# TPS65131.net
KiCad netlist of a schematic drawn in Altium Designer
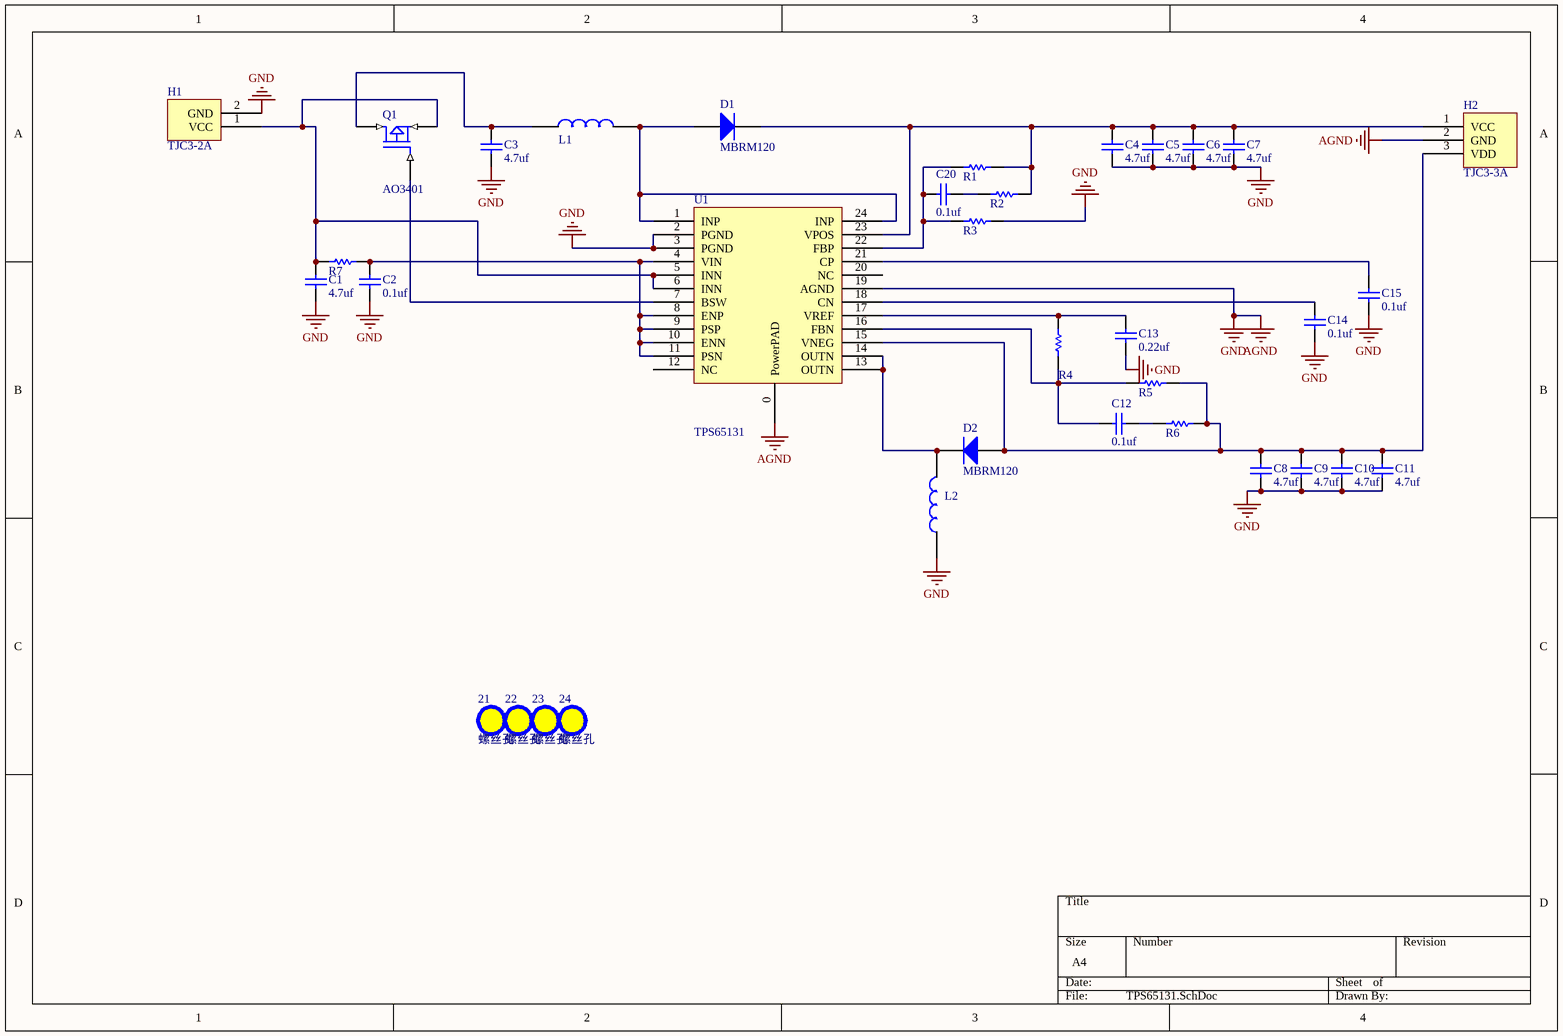
[diagram p0: TPS65131.SchDoc]

(export (version "E")
  (design (tool "Eeschema 10.0.6"))
  (components
    (comp (ref "21") (value "螺丝孔") (footprint "固定过孔") (libsource (lib "Schlib1") (part "螺丝孔")))
    (comp (ref "22") (value "螺丝孔") (footprint "固定过孔") (libsource (lib "Schlib1") (part "螺丝孔")))
    (comp (ref "23") (value "螺丝孔") (footprint "固定过孔") (libsource (lib "Schlib1") (part "螺丝孔")))
    (comp (ref "24") (value "螺丝孔") (footprint "固定过孔") (libsource (lib "Schlib1") (part "螺丝孔")))
    (comp (ref "C1")
      (value "Cap1")
      (footprint "0805")
      (fields (field (name "值") "4.7uf"))
      (libsource (lib "Schlib1") (part "Cap1"))
    )
    (comp (ref "C2")
      (value "Cap1")
      (footprint "0805")
      (fields (field (name "值") "0.1uf"))
      (libsource (lib "Schlib1") (part "Cap1"))
    )
    (comp (ref "C3")
      (value "Cap1")
      (footprint "0805")
      (fields (field (name "值") "4.7uf"))
      (libsource (lib "Schlib1") (part "Cap1"))
    )
    (comp (ref "C4")
      (value "Cap1")
      (footprint "0805")
      (fields (field (name "值") "4.7uf"))
      (libsource (lib "Schlib1") (part "Cap1"))
    )
    (comp (ref "C5")
      (value "Cap1")
      (footprint "0805")
      (fields (field (name "值") "4.7uf"))
      (libsource (lib "Schlib1") (part "Cap1"))
    )
    (comp (ref "C6")
      (value "Cap1")
      (footprint "0805")
      (fields (field (name "值") "4.7uf"))
      (libsource (lib "Schlib1") (part "Cap1"))
    )
    (comp (ref "C7")
      (value "Cap1")
      (footprint "0805")
      (fields (field (name "值") "4.7uf"))
      (libsource (lib "Schlib1") (part "Cap1"))
    )
    (comp (ref "C8")
      (value "Cap1")
      (footprint "0805")
      (fields (field (name "值") "4.7uf"))
      (libsource (lib "Schlib1") (part "Cap1"))
    )
    (comp (ref "C9")
      (value "Cap1")
      (footprint "0805")
      (fields (field (name "值") "4.7uf"))
      (libsource (lib "Schlib1") (part "Cap1"))
    )
    (comp (ref "C10")
      (value "Cap1")
      (footprint "0805")
      (fields (field (name "值") "4.7uf"))
      (libsource (lib "Schlib1") (part "Cap1"))
    )
    (comp (ref "C11")
      (value "Cap1")
      (footprint "0805")
      (fields (field (name "值") "4.7uf"))
      (libsource (lib "Schlib1") (part "Cap1"))
    )
    (comp (ref "C12")
      (value "Cap1")
      (footprint "0805")
      (fields (field (name "值") "0.1uf"))
      (libsource (lib "Schlib1") (part "Cap1"))
    )
    (comp (ref "C13")
      (value "Cap1")
      (footprint "0805")
      (fields (field (name "值") "0.22uf"))
      (libsource (lib "Schlib1") (part "Cap1"))
    )
    (comp (ref "C14")
      (value "Cap1")
      (footprint "0805")
      (fields (field (name "值") "0.1uf"))
      (libsource (lib "Schlib1") (part "Cap1"))
    )
    (comp (ref "C15")
      (value "Cap1")
      (footprint "0805")
      (fields (field (name "值") "0.1uf"))
      (libsource (lib "Schlib1") (part "Cap1"))
    )
    (comp (ref "C20")
      (value "Cap1")
      (footprint "0805")
      (fields (field (name "值") "0.1uf"))
      (libsource (lib "Schlib1") (part "Cap1"))
    )
    (comp (ref "D1") (value "MBRM120") (footprint "SMB") (libsource (lib "Schlib1") (part "MBRM120")))
    (comp (ref "D2") (value "MBRM120") (footprint "SMB") (libsource (lib "Schlib1") (part "MBRM120")))
    (comp (ref "H1") (value "TJC3-2A") (footprint "TJC3-2A") (libsource (lib "Schlib1") (part "TJC3-2A")))
    (comp (ref "H2") (value "TJC3-3A") (footprint "TJC3-3A") (libsource (lib "Schlib1") (part "TJC3-3A")))
    (comp (ref "L1") (value "SMD") (footprint "功率电感-12x12 - duplicate") (libsource (lib "") (part "功率电感_1")))
    (comp (ref "L2")
      (value "SMD")
      (footprint "功率电感-12x12 - duplicate")
      (libsource (lib "Schlib1") (part "功率电感"))
    )
    (comp (ref "Q1") (value "AO3401") (footprint "SOT-23") (libsource (lib "Schlib1") (part "AO3401")))
    (comp (ref "R1") (value "RES") (footprint "0805") (libsource (lib "Schlib1") (part "RES")))
    (comp (ref "R2") (value "RES") (footprint "0805") (libsource (lib "Schlib1") (part "RES")))
    (comp (ref "R3") (value "RES") (footprint "0805") (libsource (lib "Schlib1") (part "RES")))
    (comp (ref "R4") (value "RES") (footprint "0805") (libsource (lib "Schlib1") (part "RES")))
    (comp (ref "R5") (value "RES") (footprint "0805") (libsource (lib "Schlib1") (part "RES")))
    (comp (ref "R6") (value "RES") (footprint "0805") (libsource (lib "Schlib1") (part "RES")))
    (comp (ref "R7") (value "RES") (footprint "0805") (libsource (lib "Schlib1") (part "RES")))
    (comp (ref "U1")
      (value "TPS65131")
      (footprint "LC-QFN-24_4x4x05P")
      (libsource (lib "Schlib1") (part "TPS65131"))
    )
  )
  (nets
    (net (code "1") (name "AGND") (class "Default")
      (node (ref "C1") (pin "1") (pinfunction "1_1") (pintype "passive"))
      (node (ref "C10") (pin "1") (pinfunction "1_1") (pintype "passive"))
      (node (ref "C11") (pin "1") (pinfunction "1_1") (pintype "passive"))
      (node (ref "C13") (pin "2") (pinfunction "2_2") (pintype "passive"))
      (node (ref "C14") (pin "2") (pinfunction "2_2") (pintype "passive"))
      (node (ref "C15") (pin "2") (pinfunction "2_2") (pintype "passive"))
      (node (ref "C2") (pin "1") (pinfunction "1_1") (pintype "passive"))
      (node (ref "C3") (pin "1") (pinfunction "1_1") (pintype "passive"))
      (node (ref "C4") (pin "1") (pinfunction "1_1") (pintype "passive"))
      (node (ref "C5") (pin "1") (pinfunction "1_1") (pintype "passive"))
      (node (ref "C6") (pin "1") (pinfunction "1_1") (pintype "passive"))
      (node (ref "C7") (pin "1") (pinfunction "1_1") (pintype "passive"))
      (node (ref "C8") (pin "1") (pinfunction "1_1") (pintype "passive"))
      (node (ref "C9") (pin "1") (pinfunction "1_1") (pintype "passive"))
      (node (ref "H1") (pin "2") (pinfunction "GND_2") (pintype "passive"))
      (node (ref "H2") (pin "2") (pinfunction "GND_2") (pintype "passive"))
      (node (ref "L2") (pin "1") (pintype "passive"))
      (node (ref "R3") (pin "2") (pinfunction "2_2") (pintype "passive"))
      (node (ref "U1") (pin "0") (pinfunction "PowerPAD_0") (pintype "passive"))
      (node (ref "U1") (pin "19") (pinfunction "AGND_19") (pintype "passive"))
      (node (ref "U1") (pin "2") (pinfunction "PGND_2") (pintype "passive"))
      (node (ref "U1") (pin "3") (pinfunction "PGND_3") (pintype "passive"))
    )
    (net (code "2") (name "Net-(C12-Pad1)") (class "Default")
      (node (ref "C12") (pin "1") (pinfunction "1_1") (pintype "passive"))
      (node (ref "R6") (pin "2") (pinfunction "2_2") (pintype "passive"))
    )
    (net (code "3") (name "Net-(C20-Pad2)") (class "Default")
      (node (ref "C20") (pin "2") (pinfunction "2_2") (pintype "passive"))
      (node (ref "R2") (pin "1") (pinfunction "1_1") (pintype "passive"))
    )
    (net (code "4") (name "Net-(D1-A)") (class "Default")
      (node (ref "D1") (pin "1") (pinfunction "A_1") (pintype "passive"))
      (node (ref "L1") (pin "2") (pintype "passive"))
      (node (ref "U1") (pin "1") (pinfunction "INP_1") (pintype "passive"))
      (node (ref "U1") (pin "24") (pinfunction "INP_24") (pintype "passive"))
    )
    (net (code "5") (name "Net-(D1-K)") (class "Default")
      (node (ref "C4") (pin "2") (pinfunction "2_2") (pintype "passive"))
      (node (ref "C5") (pin "2") (pinfunction "2_2") (pintype "passive"))
      (node (ref "C6") (pin "2") (pinfunction "2_2") (pintype "passive"))
      (node (ref "C7") (pin "2") (pinfunction "2_2") (pintype "passive"))
      (node (ref "D1") (pin "2") (pinfunction "K_2") (pintype "passive"))
      (node (ref "H2") (pin "1") (pinfunction "VCC_1") (pintype "passive"))
      (node (ref "R1") (pin "2") (pinfunction "2_2") (pintype "passive"))
      (node (ref "R2") (pin "2") (pinfunction "2_2") (pintype "passive"))
      (node (ref "U1") (pin "23") (pinfunction "VPOS_23") (pintype "passive"))
    )
    (net (code "6") (name "Net-(D2-A)") (class "Default")
      (node (ref "C10") (pin "2") (pinfunction "2_2") (pintype "passive"))
      (node (ref "C11") (pin "2") (pinfunction "2_2") (pintype "passive"))
      (node (ref "C8") (pin "2") (pinfunction "2_2") (pintype "passive"))
      (node (ref "C9") (pin "2") (pinfunction "2_2") (pintype "passive"))
      (node (ref "D2") (pin "1") (pinfunction "A_1") (pintype "passive"))
      (node (ref "H2") (pin "3") (pinfunction "VDD_3") (pintype "passive"))
      (node (ref "R5") (pin "1") (pinfunction "1_1") (pintype "passive"))
      (node (ref "R6") (pin "1") (pinfunction "1_1") (pintype "passive"))
      (node (ref "U1") (pin "15") (pinfunction "VNEG_15") (pintype "passive"))
    )
    (net (code "7") (name "Net-(D2-K)") (class "Default")
      (node (ref "D2") (pin "2") (pinfunction "K_2") (pintype "passive"))
      (node (ref "L2") (pin "2") (pintype "passive"))
      (node (ref "U1") (pin "13") (pinfunction "OUTN_13") (pintype "passive"))
      (node (ref "U1") (pin "14") (pinfunction "OUTN_14") (pintype "passive"))
    )
    (net (code "8") (name "Net-(H1-VCC)") (class "Default")
      (node (ref "C1") (pin "2") (pinfunction "2_2") (pintype "passive"))
      (node (ref "H1") (pin "1") (pinfunction "VCC_1") (pintype "passive"))
      (node (ref "Q1") (pin "3") (pinfunction "S_3") (pintype "input"))
      (node (ref "R7") (pin "1") (pinfunction "1_1") (pintype "passive"))
      (node (ref "U1") (pin "5") (pinfunction "INN_5") (pintype "passive"))
      (node (ref "U1") (pin "6") (pinfunction "INN_6") (pintype "passive"))
    )
    (net (code "9") (name "Net-(Q1-D)") (class "Default")
      (node (ref "C3") (pin "2") (pinfunction "2_2") (pintype "passive"))
      (node (ref "L1") (pin "1") (pintype "passive"))
      (node (ref "Q1") (pin "2") (pinfunction "D_2") (pintype "input"))
    )
    (net (code "10") (name "Net-(Q1-G)") (class "Default")
      (node (ref "Q1") (pin "1") (pinfunction "G_1") (pintype "input"))
      (node (ref "U1") (pin "7") (pinfunction "BSW_7") (pintype "passive"))
    )
    (net (code "11") (name "Net-(U1-CN)") (class "Default")
      (node (ref "C14") (pin "1") (pinfunction "1_1") (pintype "passive"))
      (node (ref "U1") (pin "18") (pinfunction "CN_18") (pintype "passive"))
    )
    (net (code "12") (name "Net-(U1-CP)") (class "Default")
      (node (ref "C15") (pin "1") (pinfunction "1_1") (pintype "passive"))
      (node (ref "U1") (pin "21") (pinfunction "CP_21") (pintype "passive"))
    )
    (net (code "13") (name "Net-(U1-ENN)") (class "Default")
      (node (ref "C2") (pin "2") (pinfunction "2_2") (pintype "passive"))
      (node (ref "R7") (pin "2") (pinfunction "2_2") (pintype "passive"))
      (node (ref "U1") (pin "10") (pinfunction "ENN_10") (pintype "passive"))
      (node (ref "U1") (pin "11") (pinfunction "PSN_11") (pintype "passive"))
      (node (ref "U1") (pin "4") (pinfunction "VIN_4") (pintype "passive"))
      (node (ref "U1") (pin "8") (pinfunction "ENP_8") (pintype "passive"))
      (node (ref "U1") (pin "9") (pinfunction "PSP_9") (pintype "passive"))
    )
    (net (code "14") (name "Net-(U1-FBN)") (class "Default")
      (node (ref "C12") (pin "2") (pinfunction "2_2") (pintype "passive"))
      (node (ref "R4") (pin "1") (pinfunction "1_1") (pintype "passive"))
      (node (ref "R5") (pin "2") (pinfunction "2_2") (pintype "passive"))
      (node (ref "U1") (pin "16") (pinfunction "FBN_16") (pintype "passive"))
    )
    (net (code "15") (name "Net-(U1-FBP)") (class "Default")
      (node (ref "C20") (pin "1") (pinfunction "1_1") (pintype "passive"))
      (node (ref "R1") (pin "1") (pinfunction "1_1") (pintype "passive"))
      (node (ref "R3") (pin "1") (pinfunction "1_1") (pintype "passive"))
      (node (ref "U1") (pin "22") (pinfunction "FBP_22") (pintype "passive"))
    )
    (net (code "16") (name "Net-(U1-VREF)") (class "Default")
      (node (ref "C13") (pin "1") (pinfunction "1_1") (pintype "passive"))
      (node (ref "R4") (pin "2") (pinfunction "2_2") (pintype "passive"))
      (node (ref "U1") (pin "17") (pinfunction "VREF_17") (pintype "passive"))
    )
    (net (code "17") (name "unconnected-(U1-NC-Pad12)") (class "Default")
      (node (ref "U1") (pin "12") (pinfunction "NC_12") (pintype "passive"))
    )
    (net (code "18") (name "unconnected-(U1-NC-Pad20)") (class "Default")
      (node (ref "U1") (pin "20") (pinfunction "NC_20") (pintype "passive"))
    )
  )
)
